# Pr7.net
KiCad netlist of a schematic drawn in Altium Designer
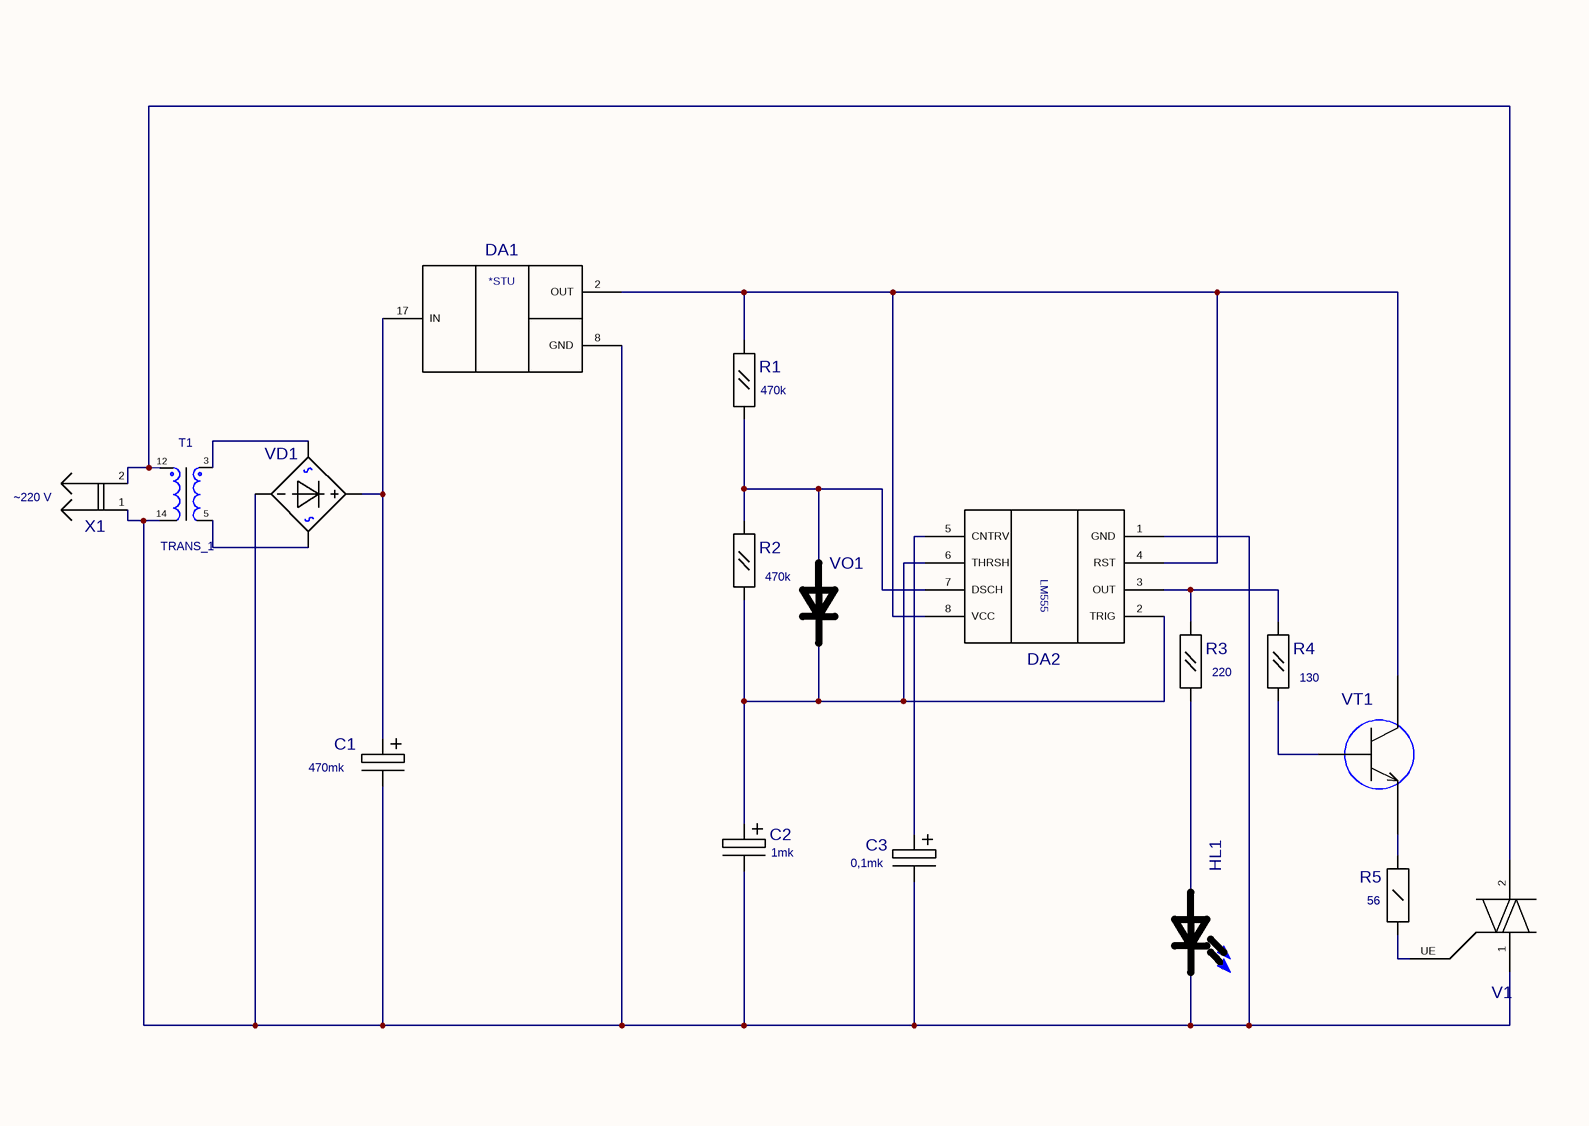
[diagram p0: Pr7.SCHDOC]

(export (version "E")
  (design (tool "Eeschema 10.0.6"))
  (components
    (comp (ref "C1")
      (value "470mk")
      (footprint "R50-35-08XX_K5035-2R")
      (description "К50-35-470МКФ-10В")
      (libsource (lib "Kondensator_DIP") (part "К50-35-470МКФ-10В"))
    )
    (comp (ref "C2")
      (value "1mk")
      (footprint "К50-35-0511_K5035-1R")
      (description "К50-35-1МКФ-50В")
      (libsource (lib "Kondensator_DIP") (part "К50-35-1МКФ-50В"))
    )
    (comp (ref "C3")
      (value "0,1mk")
      (footprint "К50-35-08XX-Г_K5035-2R")
      (description "К50-35-0,1МКФ-50В")
      (libsource (lib "Kondensator_DIP") (part "К50-35-0,1МКФ-50В"))
    )
    (comp (ref "DA1")
      (value "КР142ЕН5А")
      (footprint "TO-220-KT-28-2")
      (libsource (lib "*") (part "КР142ЕН5А"))
    )
    (comp (ref "DA2") (value "LM555CM") (footprint "SO-8") (libsource (lib "*") (part "LM555CM")))
    (comp (ref "HL1") (value "ИПД156") (footprint "3528") (libsource (lib "*") (part "ИПД156")))
    (comp (ref "R1")
      (value "470k")
      (footprint "C2-33H-0.125W")
      (description "C2-33H-0.125W_OLD_UGO")
      (fields (field (name "AUTOR") "pcbdesigner.ru"))
      (libsource (lib "*") (part "C2-33H-0.125W_OLD_UGO"))
    )
    (comp (ref "R2")
      (value "470k")
      (footprint "C2-33H-0.125W")
      (description "C2-33H-0.125W_OLD_UGO")
      (fields (field (name "AUTOR") "pcbdesigner.ru"))
      (libsource (lib "*") (part "C2-33H-0.125W_OLD_UGO"))
    )
    (comp (ref "R3")
      (value "220")
      (footprint "C2-33H-0.125W")
      (description "C2-33H-0.125W_OLD_UGO")
      (fields (field (name "AUTOR") "pcbdesigner.ru"))
      (libsource (lib "*") (part "C2-33H-0.125W_OLD_UGO"))
    )
    (comp (ref "R4")
      (value "130")
      (footprint "C2-33H-0.125W")
      (description "C2-33H-0.125W_OLD_UGO")
      (fields (field (name "AUTOR") "pcbdesigner.ru"))
      (libsource (lib "*") (part "C2-33H-0.125W_OLD_UGO"))
    )
    (comp (ref "R5")
      (value "56")
      (footprint "C2-33H-0.25W")
      (description "C2-33H-0.25W_OLD_UGO")
      (fields (field (name "AUTOR") "pcbdesigner.ru"))
      (libsource (lib "*") (part "C2-33H-0.25W_OLD_UGO"))
    )
    (comp (ref "T1")
      (value "TRANS_1")
      (footprint "TRANS_1_TRANS_1(Primary)")
      (libsource (lib "*") (part "TRANS_1"))
    )
    (comp (ref "V1")
      (value "TC122")
      (footprint "КУ202_КУ202А(Primary)")
      (libsource (lib "Diod") (part "TC122"))
    )
    (comp (ref "VD1") (value "2Д2136АС") (footprint "2Д2136АС") (libsource (lib "*") (part "2Д2136АС")))
    (comp (ref "VO1") (value "1N34") (footprint "DO-7") (libsource (lib "*") (part "1N34")))
    (comp (ref "VT1")
      (value "КТ315Б")
      (footprint "KT13_КТ315Б(KT13-1)")
      (libsource (lib "Tranzistor") (part "КТ315Б"))
    )
    (comp (ref "X1")
      (value "~220 V")
      (footprint "2XR")
      (description "2XR")
      (libsource (lib "*") (part "2XR"))
    )
  )
  (nets
    (net (code "1") (name "Net-(DA1-GND)") (class "Default")
      (node (ref "C1") (pin "2") (pinfunction "2_2") (pintype "passive"))
      (node (ref "C2") (pin "2") (pinfunction "2_2") (pintype "passive"))
      (node (ref "C3") (pin "2") (pinfunction "2_2") (pintype "passive"))
      (node (ref "DA1") (pin "8") (pinfunction "GND_8") (pintype "passive"))
      (node (ref "DA2") (pin "1") (pinfunction "GND_1") (pintype "passive"))
      (node (ref "HL1") (pin "1") (pinfunction "K_1") (pintype "passive"))
      (node (ref "T1") (pin "14") (pinfunction "14_14") (pintype "passive"))
      (node (ref "V1") (pin "1") (pinfunction "E2_1") (pintype "passive"))
      (node (ref "VD1") (pin "4") (pinfunction "-_4") (pintype "passive"))
      (node (ref "X1") (pin "1") (pinfunction "I/O1_1") (pintype "passive"))
    )
    (net (code "2") (name "Net-(DA1-IN)") (class "Default")
      (node (ref "C1") (pin "1") (pinfunction "1_1") (pintype "passive"))
      (node (ref "DA1") (pin "17") (pinfunction "IN_17") (pintype "passive"))
      (node (ref "VD1") (pin "5") (pinfunction "+_5") (pintype "passive"))
    )
    (net (code "3") (name "Net-(DA1-OUT)") (class "Default")
      (node (ref "DA1") (pin "2") (pinfunction "OUT_2") (pintype "passive"))
      (node (ref "DA2") (pin "4") (pinfunction "RST_4") (pintype "passive"))
      (node (ref "DA2") (pin "8") (pinfunction "VCC_8") (pintype "passive"))
      (node (ref "R1") (pin "1") (pinfunction "1_1") (pintype "passive"))
      (node (ref "VT1") (pin "3") (pinfunction "K_3") (pintype "passive"))
    )
    (net (code "4") (name "Net-(DA2-CNTRV)") (class "Default")
      (node (ref "C3") (pin "1") (pinfunction "1_1") (pintype "passive"))
      (node (ref "DA2") (pin "5") (pinfunction "CNTRV_5") (pintype "passive"))
    )
    (net (code "5") (name "Net-(DA2-DSCH)") (class "Default")
      (node (ref "DA2") (pin "7") (pinfunction "DSCH_7") (pintype "passive"))
      (node (ref "R1") (pin "2") (pinfunction "2_2") (pintype "passive"))
      (node (ref "R2") (pin "2") (pinfunction "2_2") (pintype "passive"))
      (node (ref "VO1") (pin "A") (pinfunction "A_A") (pintype "passive"))
    )
    (net (code "6") (name "Net-(DA2-OUT)") (class "Default")
      (node (ref "DA2") (pin "3") (pinfunction "OUT_3") (pintype "passive"))
      (node (ref "R3") (pin "2") (pinfunction "2_2") (pintype "passive"))
      (node (ref "R4") (pin "2") (pinfunction "2_2") (pintype "passive"))
    )
    (net (code "7") (name "Net-(DA2-THRSH)") (class "Default")
      (node (ref "C2") (pin "1") (pinfunction "1_1") (pintype "passive"))
      (node (ref "DA2") (pin "2") (pinfunction "TRIG_2") (pintype "passive"))
      (node (ref "DA2") (pin "6") (pinfunction "THRSH_6") (pintype "passive"))
      (node (ref "R2") (pin "1") (pinfunction "1_1") (pintype "passive"))
      (node (ref "VO1") (pin "K") (pinfunction "K_K") (pintype "passive"))
    )
    (net (code "8") (name "Net-(HL1-A)") (class "Default")
      (node (ref "HL1") (pin "2") (pinfunction "A_2") (pintype "passive"))
      (node (ref "R3") (pin "1") (pinfunction "1_1") (pintype "passive"))
    )
    (net (code "9") (name "Net-(R5-Pad1)") (class "Default")
      (node (ref "R5") (pin "1") (pinfunction "1_1") (pintype "passive"))
      (node (ref "V1") (pin "UE") (pinfunction "UE_UE") (pintype "passive"))
    )
    (net (code "10") (name "Net-(T1-Pad3)") (class "Default")
      (node (ref "T1") (pin "3") (pinfunction "3_3") (pintype "passive"))
      (node (ref "VD1") (pin "1") (pintype "passive"))
    )
    (net (code "11") (name "Net-(T1-Pad5)") (class "Default")
      (node (ref "T1") (pin "5") (pinfunction "5_5") (pintype "passive"))
      (node (ref "VD1") (pin "3") (pintype "passive"))
    )
    (net (code "12") (name "Net-(V1-E1)") (class "Default")
      (node (ref "T1") (pin "12") (pinfunction "12_12") (pintype "passive"))
      (node (ref "V1") (pin "2") (pinfunction "E1_2") (pintype "passive"))
      (node (ref "X1") (pin "2") (pinfunction "I/O2_2") (pintype "passive"))
    )
    (net (code "13") (name "Net-(VT1-B)") (class "Default")
      (node (ref "R4") (pin "1") (pinfunction "1_1") (pintype "passive"))
      (node (ref "VT1") (pin "2") (pinfunction "B_2") (pintype "passive"))
    )
    (net (code "14") (name "Net-(VT1-E)") (class "Default")
      (node (ref "R5") (pin "2") (pinfunction "2_2") (pintype "passive"))
      (node (ref "VT1") (pin "1") (pinfunction "E_1") (pintype "passive"))
    )
    (net (code "15") (name "unconnected-(DA1-Pad4)") (class "Default")
      (node (ref "DA1") (pin "4") (pintype "passive"))
    )
    (net (code "16") (name "unconnected-(V1-Pad4)") (class "Default")
      (node (ref "V1") (pin "4") (pintype "passive"))
    )
    (net (code "17") (name "unconnected-(V1-Pad5)") (class "Default")
      (node (ref "V1") (pin "5") (pintype "passive"))
    )
    (net (code "18") (name "unconnected-(VD1-Pad2)") (class "Default")
      (node (ref "VD1") (pin "2") (pintype "passive"))
    )
  )
)
